# Schematic.net
KiCad netlist of a schematic drawn in EasyEDA Pro
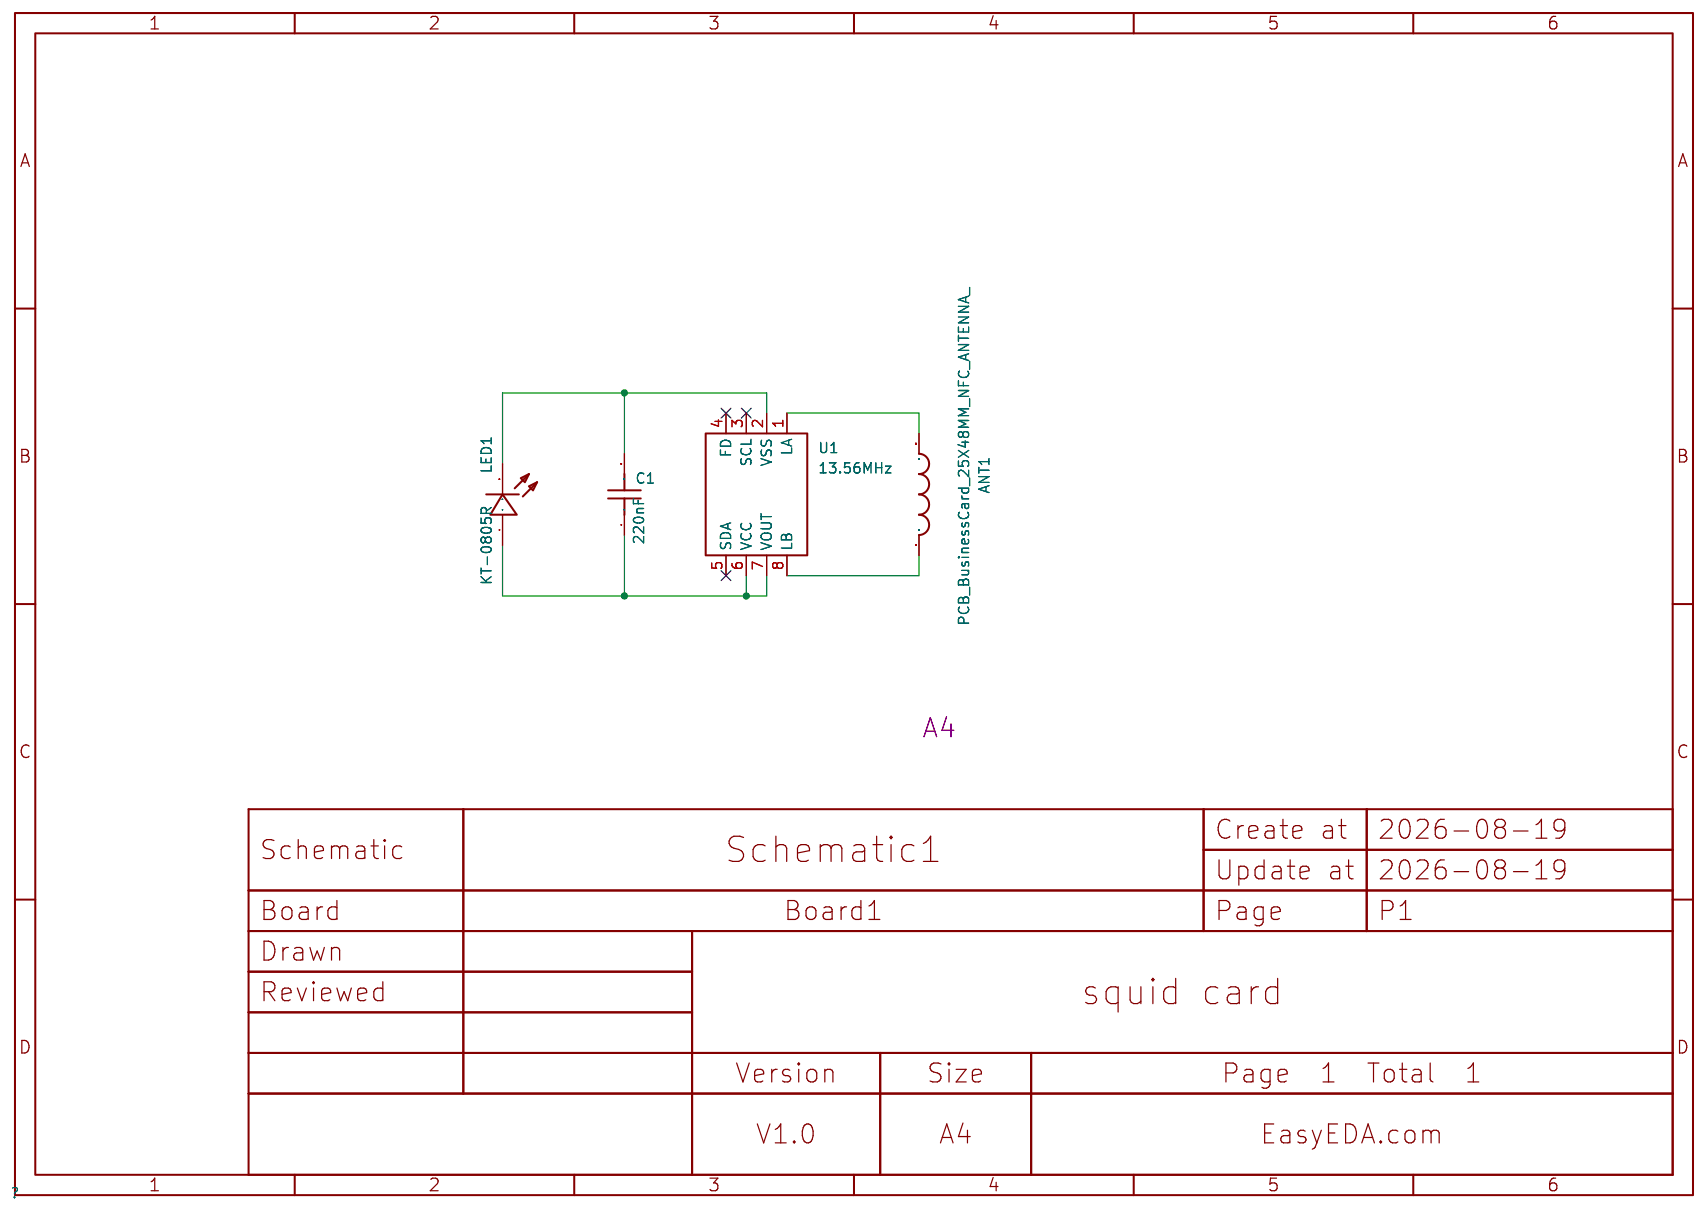
[diagram p0: schematic sheet]

(export (version "E")
  (design (tool "Eeschema 10.0.6"))
  (components
    (comp (ref "ANT1")
      (value "PCB_BusinessCard_25X48MM_NFC_ANTENNA_")
      (libsource (lib "easyedapro") (part "PCB_BusinessCard_25X48MM_NFC_ANTENNA_"))
    )
    (comp (ref "C1")
      (value "220nF")
      (footprint "easyedapro:C0603")
      (libsource (lib "easyedapro") (part "CAP_OLD"))
    )
    (comp (ref "LED1")
      (value "KT-0805R")
      (footprint "easyedapro:LED-SMD_L1.6-W0.8-R-RD")
      (fields (field (name "Manufacturer") "KENTO"))
      (libsource (lib "easyedapro") (part "KT-0603R"))
    )
    (comp (ref "U1")
      (value "13.56MHz")
      (footprint "easyedapro:XQFN-8_L1.6-W1.6-P0.50-BL_NT3H2111W0FHKH")
      (fields (field (name "Manufacturer Part") "NT3H2111W0FHKH") (field (name "Manufacturer") "NXP(恩智浦)"))
      (libsource (lib "easyedapro") (part "NT3H2111W0FHKH"))
    )
  )
  (nets
    (net (code "1") (name "Net-(LED1-A)") (class "Default")
      (node (ref "C1") (pin "1") (pinfunction "1_1") (pintype "input"))
      (node (ref "LED1") (pin "1") (pinfunction "A_1") (pintype "unspecified"))
      (node (ref "U1") (pin "6") (pinfunction "VCC_6") (pintype "unspecified"))
      (node (ref "U1") (pin "7") (pinfunction "VOUT_7") (pintype "unspecified"))
    )
    (net (code "2") (name "Net-(LED1-K)") (class "Default")
      (node (ref "C1") (pin "2") (pinfunction "2_2") (pintype "input"))
      (node (ref "LED1") (pin "2") (pinfunction "K_2") (pintype "unspecified"))
      (node (ref "U1") (pin "2") (pinfunction "VSS_2") (pintype "unspecified"))
    )
    (net (code "3") (name "Net-(U1-LA)") (class "Default")
      (node (ref "ANT1") (pin "P$1") (pinfunction "P$1_P$1") (pintype "bidirectional"))
      (node (ref "U1") (pin "1") (pinfunction "LA_1") (pintype "unspecified"))
    )
    (net (code "4") (name "Net-(U1-LB)") (class "Default")
      (node (ref "ANT1") (pin "P$2") (pinfunction "P$2_P$2") (pintype "bidirectional"))
      (node (ref "U1") (pin "8") (pinfunction "LB_8") (pintype "unspecified"))
    )
    (net (code "5") (name "unconnected-(U1-FD-Pad4)") (class "Default")
      (node (ref "U1") (pin "4") (pinfunction "FD_4") (pintype "unspecified+no_connect"))
    )
    (net (code "6") (name "unconnected-(U1-SCL-Pad3)") (class "Default")
      (node (ref "U1") (pin "3") (pinfunction "SCL_3") (pintype "unspecified+no_connect"))
    )
    (net (code "7") (name "unconnected-(U1-SDA-Pad5)") (class "Default")
      (node (ref "U1") (pin "5") (pinfunction "SDA_5") (pintype "unspecified+no_connect"))
    )
  )
)
